# main.net
KiCad netlist of a schematic drawn in EAGLE
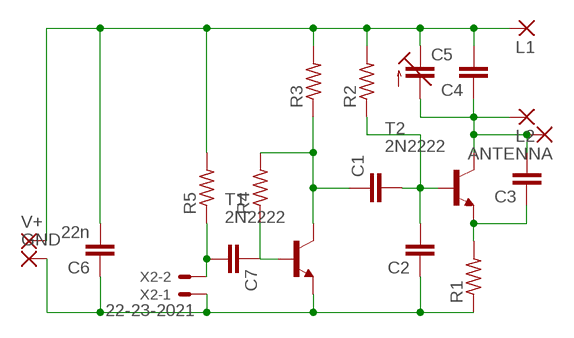
[diagram p0: schematic, sheet 1]

(export (version "E")
  (design (tool "Eeschema 10.0.6"))
  (components
    (comp (ref "ANTENNA")
      (value "2,15/1,0")
      (footprint "eagle-import:2,15_1,0")
      (libsource (lib "eagle-import") (part "2,15/1,0"))
    )
    (comp (ref "C1")
      (value "C2.5/4")
      (footprint "eagle-import:C2.5-4")
      (libsource (lib "eagle-import") (part "C2.5/4"))
    )
    (comp (ref "C2")
      (value "C2.5/4")
      (footprint "eagle-import:C2.5-4")
      (libsource (lib "eagle-import") (part "C2.5/4"))
    )
    (comp (ref "C3")
      (value "C2.5/4")
      (footprint "eagle-import:C2.5-4")
      (libsource (lib "eagle-import") (part "C2.5/4"))
    )
    (comp (ref "C4")
      (value "C2.5/4")
      (footprint "eagle-import:C2.5-4")
      (libsource (lib "eagle-import") (part "C2.5/4"))
    )
    (comp (ref "C5")
      (value "C-TRIMM3050.504")
      (footprint "eagle-import:CTRIM3050.504")
      (libsource (lib "eagle-import") (part "C-TRIMM3050.504"))
    )
    (comp (ref "C6")
      (value "22n")
      (footprint "eagle-import:C2.5-4")
      (libsource (lib "eagle-import") (part "C2.5/4"))
    )
    (comp (ref "C7")
      (value "C2.5/4")
      (footprint "eagle-import:C2.5-4")
      (libsource (lib "eagle-import") (part "C2.5/4"))
    )
    (comp (ref "GND")
      (value "2,15/1,0")
      (footprint "eagle-import:2,15_1,0")
      (libsource (lib "eagle-import") (part "2,15/1,0"))
    )
    (comp (ref "L1")
      (value "2,15/1,0")
      (footprint "eagle-import:2,15_1,0")
      (libsource (lib "eagle-import") (part "2,15/1,0"))
    )
    (comp (ref "L2")
      (value "2,15/1,0")
      (footprint "eagle-import:2,15_1,0")
      (libsource (lib "eagle-import") (part "2,15/1,0"))
    )
    (comp (ref "R1")
      (value "R-US_0204/2V")
      (footprint "eagle-import:0204V")
      (libsource (lib "eagle-import") (part "R-US_0204/2V"))
    )
    (comp (ref "R2")
      (value "R-US_0204/2V")
      (footprint "eagle-import:0204V")
      (libsource (lib "eagle-import") (part "R-US_0204/2V"))
    )
    (comp (ref "R3")
      (value "R-US_0204/2V")
      (footprint "eagle-import:0204V")
      (libsource (lib "eagle-import") (part "R-US_0204/2V"))
    )
    (comp (ref "R4")
      (value "R-US_0204/2V")
      (footprint "eagle-import:0204V")
      (libsource (lib "eagle-import") (part "R-US_0204/2V"))
    )
    (comp (ref "R5")
      (value "R-US_0204/2V")
      (footprint "eagle-import:0204V")
      (libsource (lib "eagle-import") (part "R-US_0204/2V"))
    )
    (comp (ref "T1")
      (value "2N2222")
      (footprint "eagle-import:TO92-EBC-OVAL")
      (libsource (lib "eagle-import") (part "2N2222"))
    )
    (comp (ref "T2")
      (value "2N2222")
      (footprint "eagle-import:TO92-EBC-OVAL")
      (libsource (lib "eagle-import") (part "2N2222"))
    )
    (comp (ref "V+")
      (value "2,15/1,0")
      (footprint "eagle-import:2,15_1,0")
      (libsource (lib "eagle-import") (part "2,15/1,0"))
    )
    (comp (ref "X2")
      (value "22-23-2021")
      (footprint "eagle-import:22-23-2021")
      (fields (field (name "MF") "MOLEX"))
      (libsource (lib "eagle-import") (part "22-23-2021"))
    )
  )
  (nets
    (net (code "1") (name "Net-(ANTENNA-P)") (class "Default")
      (node (ref "ANTENNA") (pin "1") (pinfunction "P_1") (pintype "passive"))
      (node (ref "C3") (pin "2") (pinfunction "2_2") (pintype "passive"))
      (node (ref "C4") (pin "1") (pinfunction "1_1") (pintype "passive"))
      (node (ref "C5") (pin "2") (pinfunction "A_2") (pintype "passive"))
      (node (ref "L2") (pin "1") (pinfunction "P_1") (pintype "passive"))
      (node (ref "T2") (pin "C") (pinfunction "C_C") (pintype "passive"))
    )
    (net (code "2") (name "Net-(C1-Pad1)") (class "Default")
      (node (ref "C1") (pin "1") (pinfunction "1_1") (pintype "passive"))
      (node (ref "R3") (pin "1") (pinfunction "1_1") (pintype "passive"))
      (node (ref "R4") (pin "2") (pinfunction "2_2") (pintype "passive"))
      (node (ref "T1") (pin "C") (pinfunction "C_C") (pintype "passive"))
    )
    (net (code "3") (name "Net-(C1-Pad2)") (class "Default")
      (node (ref "C1") (pin "2") (pinfunction "2_2") (pintype "passive"))
      (node (ref "C2") (pin "2") (pinfunction "2_2") (pintype "passive"))
      (node (ref "R2") (pin "1") (pinfunction "1_1") (pintype "passive"))
      (node (ref "T2") (pin "B") (pinfunction "B_B") (pintype "passive"))
    )
    (net (code "4") (name "Net-(C3-Pad1)") (class "Default")
      (node (ref "C3") (pin "1") (pinfunction "1_1") (pintype "passive"))
      (node (ref "R1") (pin "2") (pinfunction "2_2") (pintype "passive"))
      (node (ref "T2") (pin "E") (pinfunction "E_E") (pintype "passive"))
    )
    (net (code "5") (name "Net-(C5-E)") (class "Default")
      (node (ref "C4") (pin "2") (pinfunction "2_2") (pintype "passive"))
      (node (ref "C5") (pin "1") (pinfunction "E_1") (pintype "passive"))
      (node (ref "C6") (pin "2") (pinfunction "2_2") (pintype "passive"))
      (node (ref "L1") (pin "1") (pinfunction "P_1") (pintype "passive"))
      (node (ref "R2") (pin "2") (pinfunction "2_2") (pintype "passive"))
      (node (ref "R3") (pin "2") (pinfunction "2_2") (pintype "passive"))
      (node (ref "R5") (pin "2") (pinfunction "2_2") (pintype "passive"))
      (node (ref "V+") (pin "1") (pinfunction "P_1") (pintype "passive"))
    )
    (net (code "6") (name "Net-(C7-Pad1)") (class "Default")
      (node (ref "C7") (pin "1") (pinfunction "1_1") (pintype "passive"))
      (node (ref "R4") (pin "1") (pinfunction "1_1") (pintype "passive"))
      (node (ref "T1") (pin "B") (pinfunction "B_B") (pintype "passive"))
    )
    (net (code "7") (name "Net-(GND-P)") (class "Default")
      (node (ref "C2") (pin "1") (pinfunction "1_1") (pintype "passive"))
      (node (ref "C6") (pin "1") (pinfunction "1_1") (pintype "passive"))
      (node (ref "GND") (pin "1") (pinfunction "P_1") (pintype "passive"))
      (node (ref "R1") (pin "1") (pinfunction "1_1") (pintype "passive"))
      (node (ref "T1") (pin "E") (pinfunction "E_E") (pintype "passive"))
      (node (ref "X2") (pin "1") (pinfunction "S_1") (pintype "passive"))
    )
    (net (code "8") (name "Net-(X2B-S)") (class "Default")
      (node (ref "C7") (pin "2") (pinfunction "2_2") (pintype "passive"))
      (node (ref "R5") (pin "1") (pinfunction "1_1") (pintype "passive"))
      (node (ref "X2") (pin "2") (pinfunction "S_2") (pintype "passive"))
    )
  )
)
